# ProProject__V1_1_2024-06-03.net
KiCad netlist of a schematic drawn in EasyEDA Pro
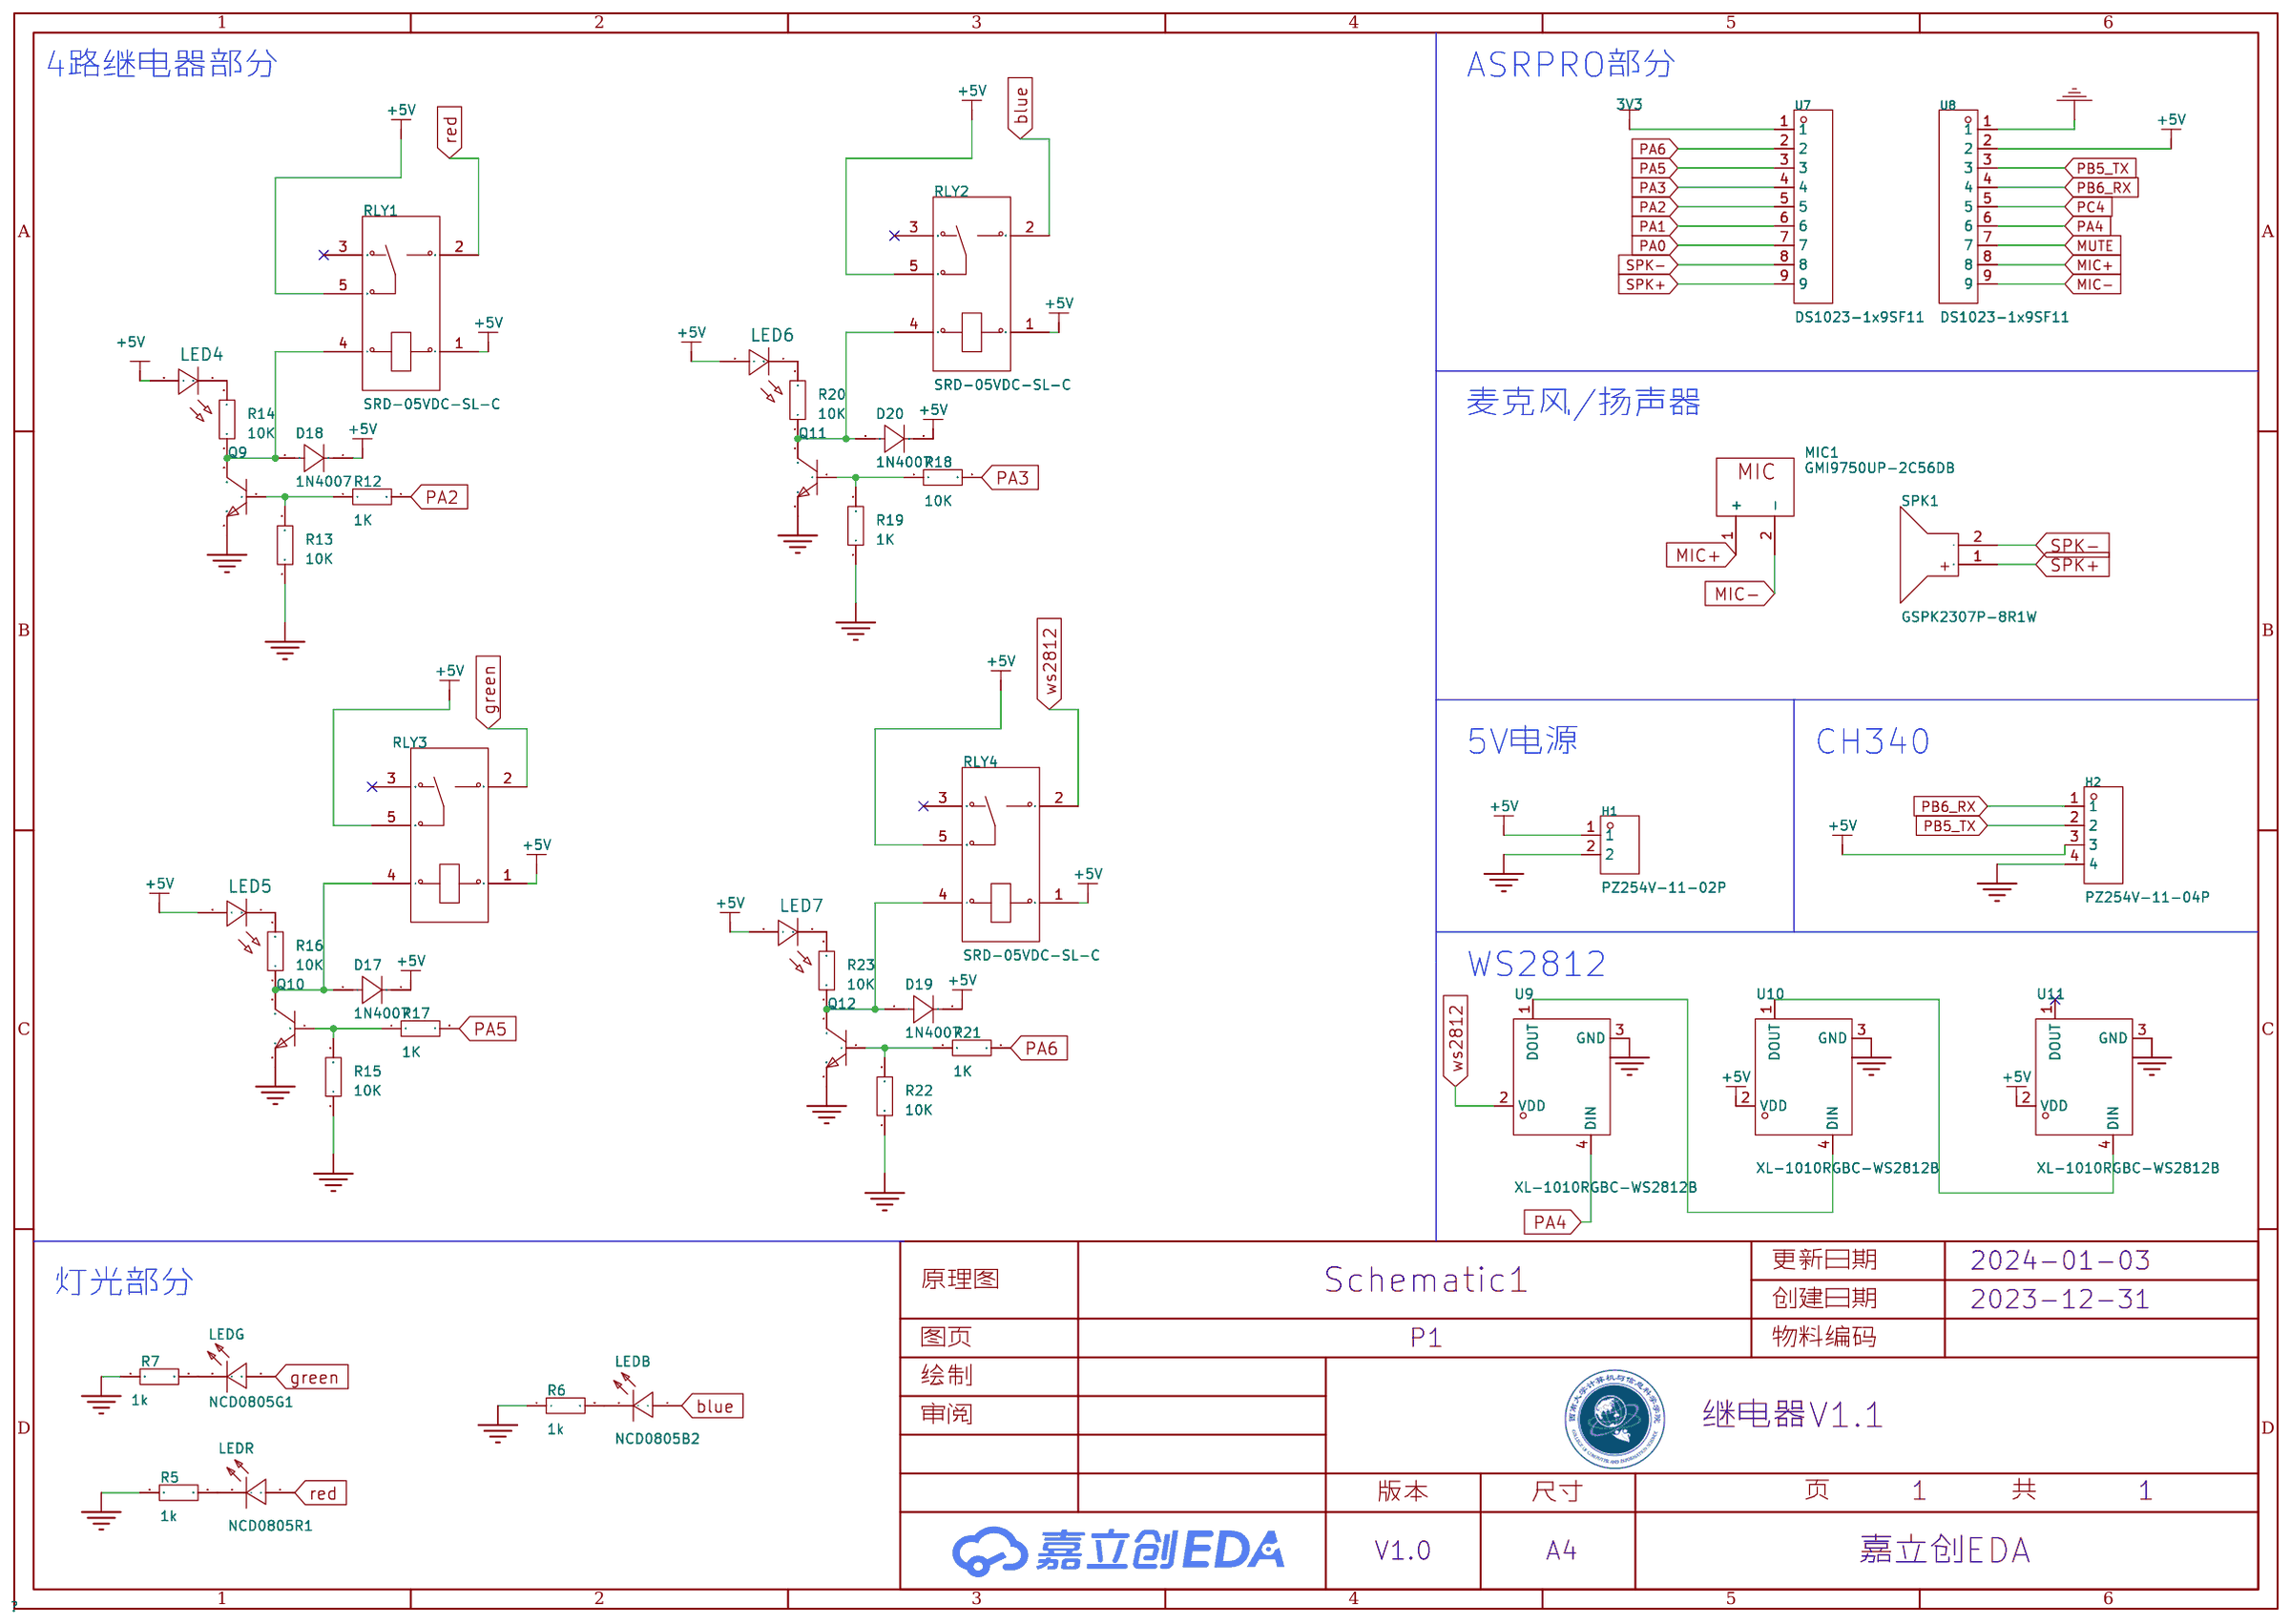
[diagram p0: schematic sheet]

(export (version "E")
  (design (tool "Eeschema 10.0.6"))
  (components
    (comp (ref "D17")
      (value "1N4007")
      (footprint "easyedapro:SMA_L4.3-W2.5-LS5.0-RD")
      (description "二极管配置:独立式;正向压降(Vf):1.1V@1A;直流反向耐压(Vr):1kV;平均整流电流(Io):1A;")
      (fields (field (name "Manufacturer") "TWGMC(台湾迪嘉)"))
      (libsource (lib "easyedapro") (part "1N4007_C727081"))
    )
    (comp (ref "D18")
      (value "1N4007")
      (footprint "easyedapro:SMA_L4.3-W2.5-LS5.0-RD")
      (description "二极管配置:独立式;正向压降(Vf):1.1V@1A;直流反向耐压(Vr):1kV;平均整流电流(Io):1A;")
      (fields (field (name "Manufacturer") "TWGMC(台湾迪嘉)"))
      (libsource (lib "easyedapro") (part "1N4007_C727081"))
    )
    (comp (ref "D19")
      (value "1N4007")
      (footprint "easyedapro:SMA_L4.3-W2.5-LS5.0-RD")
      (description "二极管配置:独立式;正向压降(Vf):1.1V@1A;直流反向耐压(Vr):1kV;平均整流电流(Io):1A;")
      (fields (field (name "Manufacturer") "TWGMC(台湾迪嘉)"))
      (libsource (lib "easyedapro") (part "1N4007_C727081"))
    )
    (comp (ref "D20")
      (value "1N4007")
      (footprint "easyedapro:SMA_L4.3-W2.5-LS5.0-RD")
      (description "二极管配置:独立式;正向压降(Vf):1.1V@1A;直流反向耐压(Vr):1kV;平均整流电流(Io):1A;")
      (fields (field (name "Manufacturer") "TWGMC(台湾迪嘉)"))
      (libsource (lib "easyedapro") (part "1N4007_C727081"))
    )
    (comp (ref "H1")
      (value "PZ254V-11-02P")
      (footprint "easyedapro:HDR-TH_2P-P2.54-V-M")
      (fields (field (name "Manufacturer") "XFCN(兴飞)"))
      (libsource (lib "easyedapro") (part "PZ254V-11-02P"))
    )
    (comp (ref "H2")
      (value "PZ254V-11-04P")
      (footprint "easyedapro:HDR-TH_4P-P2.54-V-M")
      (fields (field (name "Manufacturer") "XFCN(兴飞)"))
      (libsource (lib "easyedapro") (part "PZ254V-11-04P_C2691448"))
    )
    (comp (ref "LED4")
      (value "~")
      (footprint "easyedapro:LED_0603")
      (libsource (lib "easyedapro") (part "LED_R"))
    )
    (comp (ref "LED5")
      (value "~")
      (footprint "easyedapro:LED_0603")
      (libsource (lib "easyedapro") (part "LED_R"))
    )
    (comp (ref "LED6")
      (value "~")
      (footprint "easyedapro:LED_0603")
      (libsource (lib "easyedapro") (part "LED_R"))
    )
    (comp (ref "LED7")
      (value "~")
      (footprint "easyedapro:LED_0603")
      (libsource (lib "easyedapro") (part "LED_R"))
    )
    (comp (ref "LEDB")
      (value "NCD0805B2")
      (footprint "easyedapro:LED0805-R-RD")
      (description "发光颜色:蓝色;功率:72mW;透镜颜色:无色透明;主波长:468nm~478nm;发光强度:20mcd~55mcd;发光角度:130°;工作温度:-30°C~+85°C;")
      (fields (field (name "Manufacturer") "国星光电"))
      (libsource (lib "easyedapro") (part "FC-A2012BK-470H2"))
    )
    (comp (ref "LEDG")
      (value "NCD0805G1")
      (footprint "easyedapro:LED0805-R-RD")
      (description "发光颜色:翠绿色;功率:72mW;透镜颜色:无色透明;主波长:525nm~537.5nm;发光强度:180mcd~400mcd;发光角度:130°;工作温度:-30°C~+85°C;")
      (fields (field (name "Manufacturer") "国星光电"))
      (libsource (lib "easyedapro") (part "FC-2012UGK-520D5"))
    )
    (comp (ref "LEDR")
      (value "NCD0805R1")
      (footprint "easyedapro:LED0805-R-RD")
      (fields (field (name "Manufacturer") "国星光电"))
      (libsource (lib "easyedapro") (part "FC-2012HRK-620D"))
    )
    (comp (ref "MIC1")
      (value "GMI9750UP-2C56DB")
      (footprint "easyedapro:MIC-TH_BD9.7-P2.50-D0.8-L-FD")
      (fields (field (name "Manufacturer") "INGHAi(赢海)"))
      (libsource (lib "easyedapro") (part "GMI9750UP-2C56DB"))
    )
    (comp (ref "Q9")
      (value "~")
      (footprint "easyedapro:S8050_SOT-23")
      (libsource (lib "easyedapro") (part "NPN"))
    )
    (comp (ref "Q10")
      (value "~")
      (footprint "easyedapro:S8050_SOT-23")
      (libsource (lib "easyedapro") (part "NPN"))
    )
    (comp (ref "Q11")
      (value "~")
      (footprint "easyedapro:S8050_SOT-23")
      (libsource (lib "easyedapro") (part "NPN"))
    )
    (comp (ref "Q12")
      (value "~")
      (footprint "easyedapro:S8050_SOT-23")
      (libsource (lib "easyedapro") (part "NPN"))
    )
    (comp (ref "R5") (value "1k") (footprint "easyedapro:R0603") (libsource (lib "easyedapro") (part "电阻")))
    (comp (ref "R6") (value "1k") (footprint "easyedapro:R0603") (libsource (lib "easyedapro") (part "电阻")))
    (comp (ref "R7") (value "1k") (footprint "easyedapro:R0603") (libsource (lib "easyedapro") (part "电阻")))
    (comp (ref "R12") (value "1K") (footprint "easyedapro:R0603") (libsource (lib "easyedapro") (part "电阻")))
    (comp (ref "R13") (value "10K") (footprint "easyedapro:R0603") (libsource (lib "easyedapro") (part "电阻")))
    (comp (ref "R14") (value "10K") (footprint "easyedapro:R0603") (libsource (lib "easyedapro") (part "电阻")))
    (comp (ref "R15") (value "10K") (footprint "easyedapro:R0603") (libsource (lib "easyedapro") (part "电阻")))
    (comp (ref "R16") (value "10K") (footprint "easyedapro:R0603") (libsource (lib "easyedapro") (part "电阻")))
    (comp (ref "R17") (value "1K") (footprint "easyedapro:R0603") (libsource (lib "easyedapro") (part "电阻")))
    (comp (ref "R18") (value "10K") (footprint "easyedapro:R0603") (libsource (lib "easyedapro") (part "电阻")))
    (comp (ref "R19") (value "1K") (footprint "easyedapro:R0603") (libsource (lib "easyedapro") (part "电阻")))
    (comp (ref "R20") (value "10K") (footprint "easyedapro:R0603") (libsource (lib "easyedapro") (part "电阻")))
    (comp (ref "R21") (value "1K") (footprint "easyedapro:R0603") (libsource (lib "easyedapro") (part "电阻")))
    (comp (ref "R22") (value "10K") (footprint "easyedapro:R0603") (libsource (lib "easyedapro") (part "电阻")))
    (comp (ref "R23") (value "10K") (footprint "easyedapro:R0603") (libsource (lib "easyedapro") (part "电阻")))
    (comp (ref "RLY1")
      (value "SRD-05VDC-SL-C")
      (footprint "easyedapro:RELAY-TH_SRD-XXVDC-XL-C")
      (description "线圈电压:5V;引脚数:5;触点形式:一组转换:1C(单刀双掷-转换);触点容量(电阻负载):-;")
      (fields (field (name "Manufacturer") "松乐"))
      (libsource (lib "easyedapro") (part "SRD-05VDC-SL-C"))
    )
    (comp (ref "RLY2")
      (value "SRD-05VDC-SL-C")
      (footprint "easyedapro:RELAY-TH_SRD-XXVDC-XL-C")
      (description "线圈电压:5V;引脚数:5;触点形式:一组转换:1C(单刀双掷-转换);触点容量(电阻负载):-;")
      (fields (field (name "Manufacturer") "松乐"))
      (libsource (lib "easyedapro") (part "SRD-05VDC-SL-C"))
    )
    (comp (ref "RLY3")
      (value "SRD-05VDC-SL-C")
      (footprint "easyedapro:RELAY-TH_SRD-XXVDC-XL-C")
      (description "线圈电压:5V;引脚数:5;触点形式:一组转换:1C(单刀双掷-转换);触点容量(电阻负载):-;")
      (fields (field (name "Manufacturer") "松乐"))
      (libsource (lib "easyedapro") (part "SRD-05VDC-SL-C"))
    )
    (comp (ref "RLY4")
      (value "SRD-05VDC-SL-C")
      (footprint "easyedapro:RELAY-TH_SRD-XXVDC-XL-C")
      (description "线圈电压:5V;引脚数:5;触点形式:一组转换:1C(单刀双掷-转换);触点容量(电阻负载):-;")
      (fields (field (name "Manufacturer") "松乐"))
      (libsource (lib "easyedapro") (part "SRD-05VDC-SL-C"))
    )
    (comp (ref "SPK1")
      (value "GSPK2307P-8R1W")
      (footprint "easyedapro:SPK-TH_BD23.0-P10.00-D0.8-L-RD")
      (fields (field (name "Manufacturer") "INGHAi(赢海)"))
      (libsource (lib "easyedapro") (part "GSPK2307P-8R1W"))
    )
    (comp (ref "U7")
      (value "DS1023-1x9SF11")
      (footprint "easyedapro:HDR-TH_9P-P2.54-V-F-1")
      (description "排母  2.54排母1x9直针，8.5mm高黑色，镀全金")
      (fields (field (name "Manufacturer") "CONNFLY"))
      (libsource (lib "easyedapro") (part "DS1023-1X9SF11"))
    )
    (comp (ref "U8")
      (value "DS1023-1x9SF11")
      (footprint "easyedapro:HDR-TH_9P-P2.54-V-F-1")
      (description "排母  2.54排母1x9直针，8.5mm高黑色，镀全金")
      (fields (field (name "Manufacturer") "CONNFLY"))
      (libsource (lib "easyedapro") (part "DS1023-1X9SF11"))
    )
    (comp (ref "U9")
      (value "XL-1010RGBC-WS2812B")
      (footprint "easyedapro:LED-SMD_4P-L1.0-W1.0-TL_XL-1010RGBC-WS2812B")
      (fields (field (name "Manufacturer") "XINGLIGHT(成兴光)"))
      (libsource (lib "easyedapro") (part "XL-1010RGBC-WS2812B"))
    )
    (comp (ref "U10")
      (value "XL-1010RGBC-WS2812B")
      (footprint "easyedapro:LED-SMD_4P-L1.0-W1.0-TL_XL-1010RGBC-WS2812B")
      (fields (field (name "Manufacturer") "XINGLIGHT(成兴光)"))
      (libsource (lib "easyedapro") (part "XL-1010RGBC-WS2812B"))
    )
    (comp (ref "U11")
      (value "XL-1010RGBC-WS2812B")
      (footprint "easyedapro:LED-SMD_4P-L1.0-W1.0-TL_XL-1010RGBC-WS2812B")
      (fields (field (name "Manufacturer") "XINGLIGHT(成兴光)"))
      (libsource (lib "easyedapro") (part "XL-1010RGBC-WS2812B"))
    )
  )
  (nets
    (net (code "1") (name "+5V") (class "Default")
      (node (ref "D17") (pin "1") (pinfunction "K_1") (pintype "unspecified"))
      (node (ref "D18") (pin "1") (pinfunction "K_1") (pintype "unspecified"))
      (node (ref "D19") (pin "1") (pinfunction "K_1") (pintype "unspecified"))
      (node (ref "D20") (pin "1") (pinfunction "K_1") (pintype "unspecified"))
      (node (ref "H1") (pin "1") (pinfunction "1_1") (pintype "input"))
      (node (ref "H2") (pin "3") (pinfunction "3_3") (pintype "input"))
      (node (ref "LED4") (pin "2") (pinfunction "A_2") (pintype "input"))
      (node (ref "LED5") (pin "2") (pinfunction "A_2") (pintype "input"))
      (node (ref "LED6") (pin "2") (pinfunction "A_2") (pintype "input"))
      (node (ref "LED7") (pin "2") (pinfunction "A_2") (pintype "input"))
      (node (ref "RLY1") (pin "1") (pinfunction "1_1") (pintype "input"))
      (node (ref "RLY1") (pin "5") (pinfunction "5_5") (pintype "input"))
      (node (ref "RLY2") (pin "1") (pinfunction "1_1") (pintype "input"))
      (node (ref "RLY2") (pin "5") (pinfunction "5_5") (pintype "input"))
      (node (ref "RLY3") (pin "1") (pinfunction "1_1") (pintype "input"))
      (node (ref "RLY3") (pin "5") (pinfunction "5_5") (pintype "input"))
      (node (ref "RLY4") (pin "1") (pinfunction "1_1") (pintype "input"))
      (node (ref "RLY4") (pin "5") (pinfunction "5_5") (pintype "input"))
      (node (ref "U10") (pin "2") (pinfunction "VDD_2") (pintype "unspecified"))
      (node (ref "U11") (pin "2") (pinfunction "VDD_2") (pintype "unspecified"))
      (node (ref "U8") (pin "2") (pinfunction "2_2") (pintype "input"))
    )
    (net (code "2") (name "3V3") (class "Default")
      (node (ref "U7") (pin "1") (pinfunction "1_1") (pintype "input"))
    )
    (net (code "3") (name "GND") (class "Default")
      (node (ref "H1") (pin "2") (pinfunction "2_2") (pintype "input"))
      (node (ref "H2") (pin "4") (pinfunction "4_4") (pintype "input"))
      (node (ref "Q10") (pin "2") (pinfunction "2_2") (pintype "unspecified"))
      (node (ref "Q11") (pin "2") (pinfunction "2_2") (pintype "unspecified"))
      (node (ref "Q12") (pin "2") (pinfunction "2_2") (pintype "unspecified"))
      (node (ref "Q9") (pin "2") (pinfunction "2_2") (pintype "unspecified"))
      (node (ref "R13") (pin "1") (pinfunction "1_1") (pintype "input"))
      (node (ref "R15") (pin "1") (pinfunction "1_1") (pintype "input"))
      (node (ref "R19") (pin "1") (pinfunction "1_1") (pintype "input"))
      (node (ref "R22") (pin "1") (pinfunction "1_1") (pintype "input"))
      (node (ref "R5") (pin "1") (pinfunction "1_1") (pintype "input"))
      (node (ref "R6") (pin "1") (pinfunction "1_1") (pintype "input"))
      (node (ref "R7") (pin "1") (pinfunction "1_1") (pintype "input"))
      (node (ref "U10") (pin "3") (pinfunction "GND_3") (pintype "unspecified"))
      (node (ref "U11") (pin "3") (pinfunction "GND_3") (pintype "unspecified"))
      (node (ref "U8") (pin "1") (pinfunction "1_1") (pintype "input"))
      (node (ref "U9") (pin "3") (pinfunction "GND_3") (pintype "unspecified"))
    )
    (net (code "4") (name "MIC+") (class "Default")
      (node (ref "MIC1") (pin "1") (pinfunction "+_1") (pintype "input"))
      (node (ref "U8") (pin "8") (pinfunction "8_8") (pintype "input"))
    )
    (net (code "5") (name "MIC-") (class "Default")
      (node (ref "MIC1") (pin "2") (pinfunction "-_2") (pintype "input"))
      (node (ref "U8") (pin "9") (pinfunction "9_9") (pintype "input"))
    )
    (net (code "6") (name "MUTE") (class "Default")
      (node (ref "U8") (pin "7") (pinfunction "7_7") (pintype "input"))
    )
    (net (code "7") (name "Net-(D17-A)") (class "Default")
      (node (ref "D17") (pin "2") (pinfunction "A_2") (pintype "unspecified"))
      (node (ref "Q10") (pin "3") (pinfunction "3_3") (pintype "unspecified"))
      (node (ref "R16") (pin "1") (pinfunction "1_1") (pintype "input"))
      (node (ref "RLY3") (pin "4") (pinfunction "4_4") (pintype "input"))
    )
    (net (code "8") (name "Net-(D18-A)") (class "Default")
      (node (ref "D18") (pin "2") (pinfunction "A_2") (pintype "unspecified"))
      (node (ref "Q9") (pin "3") (pinfunction "3_3") (pintype "unspecified"))
      (node (ref "R14") (pin "1") (pinfunction "1_1") (pintype "input"))
      (node (ref "RLY1") (pin "4") (pinfunction "4_4") (pintype "input"))
    )
    (net (code "9") (name "Net-(D19-A)") (class "Default")
      (node (ref "D19") (pin "2") (pinfunction "A_2") (pintype "unspecified"))
      (node (ref "Q12") (pin "3") (pinfunction "3_3") (pintype "unspecified"))
      (node (ref "R23") (pin "1") (pinfunction "1_1") (pintype "input"))
      (node (ref "RLY4") (pin "4") (pinfunction "4_4") (pintype "input"))
    )
    (net (code "10") (name "Net-(D20-A)") (class "Default")
      (node (ref "D20") (pin "2") (pinfunction "A_2") (pintype "unspecified"))
      (node (ref "Q11") (pin "3") (pinfunction "3_3") (pintype "unspecified"))
      (node (ref "R20") (pin "1") (pinfunction "1_1") (pintype "input"))
      (node (ref "RLY2") (pin "4") (pinfunction "4_4") (pintype "input"))
    )
    (net (code "11") (name "Net-(LED4-C)") (class "Default")
      (node (ref "LED4") (pin "1") (pinfunction "C_1") (pintype "input"))
      (node (ref "R14") (pin "2") (pinfunction "2_2") (pintype "input"))
    )
    (net (code "12") (name "Net-(LED5-C)") (class "Default")
      (node (ref "LED5") (pin "1") (pinfunction "C_1") (pintype "input"))
      (node (ref "R16") (pin "2") (pinfunction "2_2") (pintype "input"))
    )
    (net (code "13") (name "Net-(LED6-C)") (class "Default")
      (node (ref "LED6") (pin "1") (pinfunction "C_1") (pintype "input"))
      (node (ref "R20") (pin "2") (pinfunction "2_2") (pintype "input"))
    )
    (net (code "14") (name "Net-(LED7-C)") (class "Default")
      (node (ref "LED7") (pin "1") (pinfunction "C_1") (pintype "input"))
      (node (ref "R23") (pin "2") (pinfunction "2_2") (pintype "input"))
    )
    (net (code "15") (name "Net-(LEDB--)") (class "Default")
      (node (ref "LEDB") (pin "2") (pinfunction "-_2") (pintype "unspecified"))
      (node (ref "R6") (pin "2") (pinfunction "2_2") (pintype "input"))
    )
    (net (code "16") (name "Net-(LEDG-K)") (class "Default")
      (node (ref "LEDG") (pin "2") (pinfunction "K_2") (pintype "unspecified"))
      (node (ref "R7") (pin "2") (pinfunction "2_2") (pintype "input"))
    )
    (net (code "17") (name "Net-(LEDR--)") (class "Default")
      (node (ref "LEDR") (pin "2") (pinfunction "-_2") (pintype "unspecified"))
      (node (ref "R5") (pin "2") (pinfunction "2_2") (pintype "input"))
    )
    (net (code "18") (name "Net-(Q9-Pad1)") (class "Default")
      (node (ref "Q9") (pin "1") (pinfunction "1_1") (pintype "unspecified"))
      (node (ref "R12") (pin "1") (pinfunction "1_1") (pintype "input"))
      (node (ref "R13") (pin "2") (pinfunction "2_2") (pintype "input"))
    )
    (net (code "19") (name "Net-(Q10-Pad1)") (class "Default")
      (node (ref "Q10") (pin "1") (pinfunction "1_1") (pintype "unspecified"))
      (node (ref "R15") (pin "2") (pinfunction "2_2") (pintype "input"))
      (node (ref "R17") (pin "1") (pinfunction "1_1") (pintype "input"))
    )
    (net (code "20") (name "Net-(Q11-Pad1)") (class "Default")
      (node (ref "Q11") (pin "1") (pinfunction "1_1") (pintype "unspecified"))
      (node (ref "R18") (pin "1") (pinfunction "1_1") (pintype "input"))
      (node (ref "R19") (pin "2") (pinfunction "2_2") (pintype "input"))
    )
    (net (code "21") (name "Net-(Q12-Pad1)") (class "Default")
      (node (ref "Q12") (pin "1") (pinfunction "1_1") (pintype "unspecified"))
      (node (ref "R21") (pin "1") (pinfunction "1_1") (pintype "input"))
      (node (ref "R22") (pin "2") (pinfunction "2_2") (pintype "input"))
    )
    (net (code "22") (name "Net-(U10-DIN)") (class "Default")
      (node (ref "U10") (pin "4") (pinfunction "DIN_4") (pintype "unspecified"))
      (node (ref "U9") (pin "1") (pinfunction "DOUT_1") (pintype "unspecified"))
    )
    (net (code "23") (name "Net-(U10-DOUT)") (class "Default")
      (node (ref "U10") (pin "1") (pinfunction "DOUT_1") (pintype "unspecified"))
      (node (ref "U11") (pin "4") (pinfunction "DIN_4") (pintype "unspecified"))
    )
    (net (code "24") (name "PA0") (class "Default")
      (node (ref "U7") (pin "7") (pinfunction "7_7") (pintype "input"))
    )
    (net (code "25") (name "PA1") (class "Default")
      (node (ref "U7") (pin "6") (pinfunction "6_6") (pintype "input"))
    )
    (net (code "26") (name "PA2") (class "Default")
      (node (ref "R12") (pin "2") (pinfunction "2_2") (pintype "input"))
      (node (ref "U7") (pin "5") (pinfunction "5_5") (pintype "input"))
    )
    (net (code "27") (name "PA3") (class "Default")
      (node (ref "R18") (pin "2") (pinfunction "2_2") (pintype "input"))
      (node (ref "U7") (pin "4") (pinfunction "4_4") (pintype "input"))
    )
    (net (code "28") (name "PA4") (class "Default")
      (node (ref "U8") (pin "6") (pinfunction "6_6") (pintype "input"))
      (node (ref "U9") (pin "4") (pinfunction "DIN_4") (pintype "unspecified"))
    )
    (net (code "29") (name "PA5") (class "Default")
      (node (ref "R17") (pin "2") (pinfunction "2_2") (pintype "input"))
      (node (ref "U7") (pin "3") (pinfunction "3_3") (pintype "input"))
    )
    (net (code "30") (name "PA6") (class "Default")
      (node (ref "R21") (pin "2") (pinfunction "2_2") (pintype "input"))
      (node (ref "U7") (pin "2") (pinfunction "2_2") (pintype "input"))
    )
    (net (code "31") (name "PB5_TX") (class "Default")
      (node (ref "H2") (pin "2") (pinfunction "2_2") (pintype "input"))
      (node (ref "U8") (pin "3") (pinfunction "3_3") (pintype "input"))
    )
    (net (code "32") (name "PB6_RX") (class "Default")
      (node (ref "H2") (pin "1") (pinfunction "1_1") (pintype "input"))
      (node (ref "U8") (pin "4") (pinfunction "4_4") (pintype "input"))
    )
    (net (code "33") (name "PC4") (class "Default")
      (node (ref "U8") (pin "5") (pinfunction "5_5") (pintype "input"))
    )
    (net (code "34") (name "SPK+") (class "Default")
      (node (ref "SPK1") (pin "1") (pinfunction "+_1") (pintype "input"))
      (node (ref "U7") (pin "9") (pinfunction "9_9") (pintype "input"))
    )
    (net (code "35") (name "SPK-") (class "Default")
      (node (ref "SPK1") (pin "2") (pinfunction "-_2") (pintype "input"))
      (node (ref "U7") (pin "8") (pinfunction "8_8") (pintype "input"))
    )
    (net (code "36") (name "blue") (class "Default")
      (node (ref "LEDB") (pin "1") (pinfunction "+_1") (pintype "unspecified"))
      (node (ref "RLY2") (pin "2") (pinfunction "2_2") (pintype "input"))
    )
    (net (code "37") (name "green") (class "Default")
      (node (ref "LEDG") (pin "1") (pinfunction "A_1") (pintype "unspecified"))
      (node (ref "RLY3") (pin "2") (pinfunction "2_2") (pintype "input"))
    )
    (net (code "38") (name "red") (class "Default")
      (node (ref "LEDR") (pin "1") (pinfunction "+_1") (pintype "unspecified"))
      (node (ref "RLY1") (pin "2") (pinfunction "2_2") (pintype "input"))
    )
    (net (code "39") (name "unconnected-(RLY1-Pad3)") (class "Default")
      (node (ref "RLY1") (pin "3") (pinfunction "3_3") (pintype "input+no_connect"))
    )
    (net (code "40") (name "unconnected-(RLY2-Pad3)") (class "Default")
      (node (ref "RLY2") (pin "3") (pinfunction "3_3") (pintype "input+no_connect"))
    )
    (net (code "41") (name "unconnected-(RLY3-Pad3)") (class "Default")
      (node (ref "RLY3") (pin "3") (pinfunction "3_3") (pintype "input+no_connect"))
    )
    (net (code "42") (name "unconnected-(RLY4-Pad3)") (class "Default")
      (node (ref "RLY4") (pin "3") (pinfunction "3_3") (pintype "input+no_connect"))
    )
    (net (code "43") (name "unconnected-(U11-DOUT-Pad1)") (class "Default")
      (node (ref "U11") (pin "1") (pinfunction "DOUT_1") (pintype "unspecified+no_connect"))
    )
    (net (code "44") (name "ws2812") (class "Default")
      (node (ref "RLY4") (pin "2") (pinfunction "2_2") (pintype "input"))
      (node (ref "U9") (pin "2") (pinfunction "VDD_2") (pintype "unspecified"))
    )
  )
)
